# transistor-board.net
KiCad netlist of a schematic drawn in EAGLE
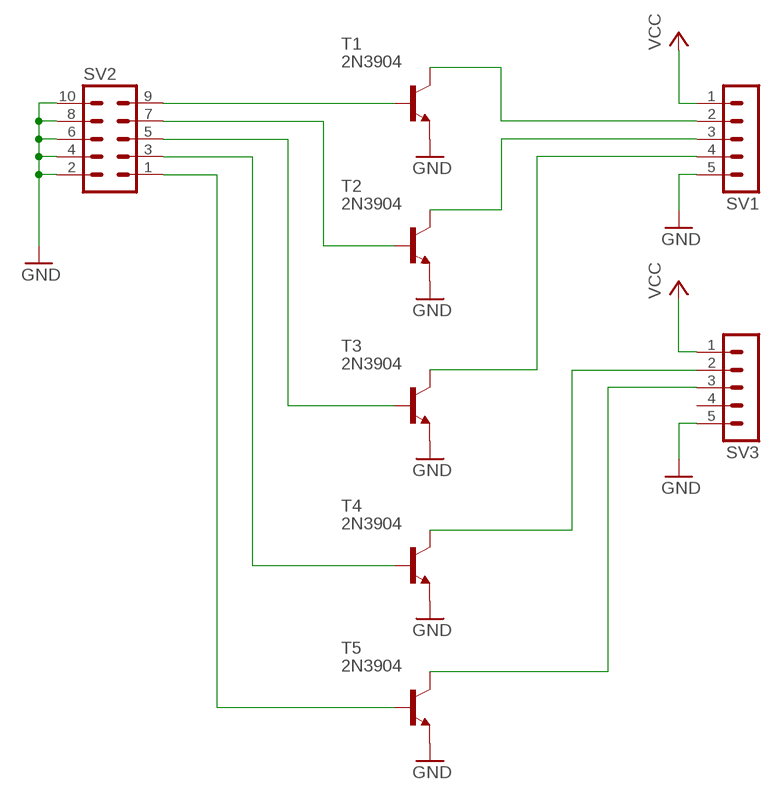
[diagram p0: schematic, sheet 1]

(export (version "E")
  (design (tool "Eeschema 10.0.6"))
  (components
    (comp (ref "SV1")
      (value "MA05-1")
      (footprint "eagle-import:MA05-1")
      (libsource (lib "eagle-import") (part "MA05-1"))
    )
    (comp (ref "SV2")
      (value "MA05-2")
      (footprint "eagle-import:MA05-2")
      (libsource (lib "eagle-import") (part "MA05-2"))
    )
    (comp (ref "SV3")
      (value "MA05-1")
      (footprint "eagle-import:MA05-1")
      (libsource (lib "eagle-import") (part "MA05-1"))
    )
    (comp (ref "T1")
      (value "2N3904")
      (footprint "eagle-import:TO92")
      (libsource (lib "eagle-import") (part "2N3904"))
    )
    (comp (ref "T2")
      (value "2N3904")
      (footprint "eagle-import:TO92")
      (libsource (lib "eagle-import") (part "2N3904"))
    )
    (comp (ref "T3")
      (value "2N3904")
      (footprint "eagle-import:TO92")
      (libsource (lib "eagle-import") (part "2N3904"))
    )
    (comp (ref "T4")
      (value "2N3904")
      (footprint "eagle-import:TO92")
      (libsource (lib "eagle-import") (part "2N3904"))
    )
    (comp (ref "T5")
      (value "2N3904")
      (footprint "eagle-import:TO92")
      (libsource (lib "eagle-import") (part "2N3904"))
    )
  )
  (nets
    (net (code "1") (name "GND") (class "Default")
      (node (ref "SV1") (pin "5") (pinfunction "5_5") (pintype "passive"))
      (node (ref "SV2") (pin "10") (pinfunction "10_10") (pintype "passive"))
      (node (ref "SV2") (pin "2") (pinfunction "2_2") (pintype "passive"))
      (node (ref "SV2") (pin "4") (pinfunction "4_4") (pintype "passive"))
      (node (ref "SV2") (pin "6") (pinfunction "6_6") (pintype "passive"))
      (node (ref "SV2") (pin "8") (pinfunction "8_8") (pintype "passive"))
      (node (ref "SV3") (pin "5") (pinfunction "5_5") (pintype "passive"))
      (node (ref "T1") (pin "3") (pinfunction "E_3") (pintype "passive"))
      (node (ref "T2") (pin "3") (pinfunction "E_3") (pintype "passive"))
      (node (ref "T3") (pin "3") (pinfunction "E_3") (pintype "passive"))
      (node (ref "T4") (pin "3") (pinfunction "E_3") (pintype "passive"))
      (node (ref "T5") (pin "3") (pinfunction "E_3") (pintype "passive"))
    )
    (net (code "2") (name "Net-(T1-B)") (class "Default")
      (node (ref "SV2") (pin "9") (pinfunction "9_9") (pintype "passive"))
      (node (ref "T1") (pin "2") (pinfunction "B_2") (pintype "passive"))
    )
    (net (code "3") (name "Net-(T1-C)") (class "Default")
      (node (ref "SV1") (pin "2") (pinfunction "2_2") (pintype "passive"))
      (node (ref "T1") (pin "1") (pinfunction "C_1") (pintype "passive"))
    )
    (net (code "4") (name "Net-(T2-B)") (class "Default")
      (node (ref "SV2") (pin "7") (pinfunction "7_7") (pintype "passive"))
      (node (ref "T2") (pin "2") (pinfunction "B_2") (pintype "passive"))
    )
    (net (code "5") (name "Net-(T2-C)") (class "Default")
      (node (ref "SV1") (pin "3") (pinfunction "3_3") (pintype "passive"))
      (node (ref "T2") (pin "1") (pinfunction "C_1") (pintype "passive"))
    )
    (net (code "6") (name "Net-(T3-B)") (class "Default")
      (node (ref "SV2") (pin "5") (pinfunction "5_5") (pintype "passive"))
      (node (ref "T3") (pin "2") (pinfunction "B_2") (pintype "passive"))
    )
    (net (code "7") (name "Net-(T3-C)") (class "Default")
      (node (ref "SV1") (pin "4") (pinfunction "4_4") (pintype "passive"))
      (node (ref "T3") (pin "1") (pinfunction "C_1") (pintype "passive"))
    )
    (net (code "8") (name "Net-(T4-B)") (class "Default")
      (node (ref "SV2") (pin "3") (pinfunction "3_3") (pintype "passive"))
      (node (ref "T4") (pin "2") (pinfunction "B_2") (pintype "passive"))
    )
    (net (code "9") (name "Net-(T4-C)") (class "Default")
      (node (ref "SV3") (pin "2") (pinfunction "2_2") (pintype "passive"))
      (node (ref "T4") (pin "1") (pinfunction "C_1") (pintype "passive"))
    )
    (net (code "10") (name "Net-(T5-B)") (class "Default")
      (node (ref "SV2") (pin "1") (pinfunction "1_1") (pintype "passive"))
      (node (ref "T5") (pin "2") (pinfunction "B_2") (pintype "passive"))
    )
    (net (code "11") (name "Net-(T5-C)") (class "Default")
      (node (ref "SV3") (pin "3") (pinfunction "3_3") (pintype "passive"))
      (node (ref "T5") (pin "1") (pinfunction "C_1") (pintype "passive"))
    )
    (net (code "12") (name "VCC") (class "Default")
      (node (ref "SV1") (pin "1") (pinfunction "1_1") (pintype "passive"))
      (node (ref "SV3") (pin "1") (pinfunction "1_1") (pintype "passive"))
    )
    (net (code "13") (name "unconnected-(SV3-Pad4)") (class "Default")
      (node (ref "SV3") (pin "4") (pinfunction "4_4") (pintype "passive"))
    )
  )
)
